# HX711_1.net
KiCad netlist of a schematic drawn in Altium Designer
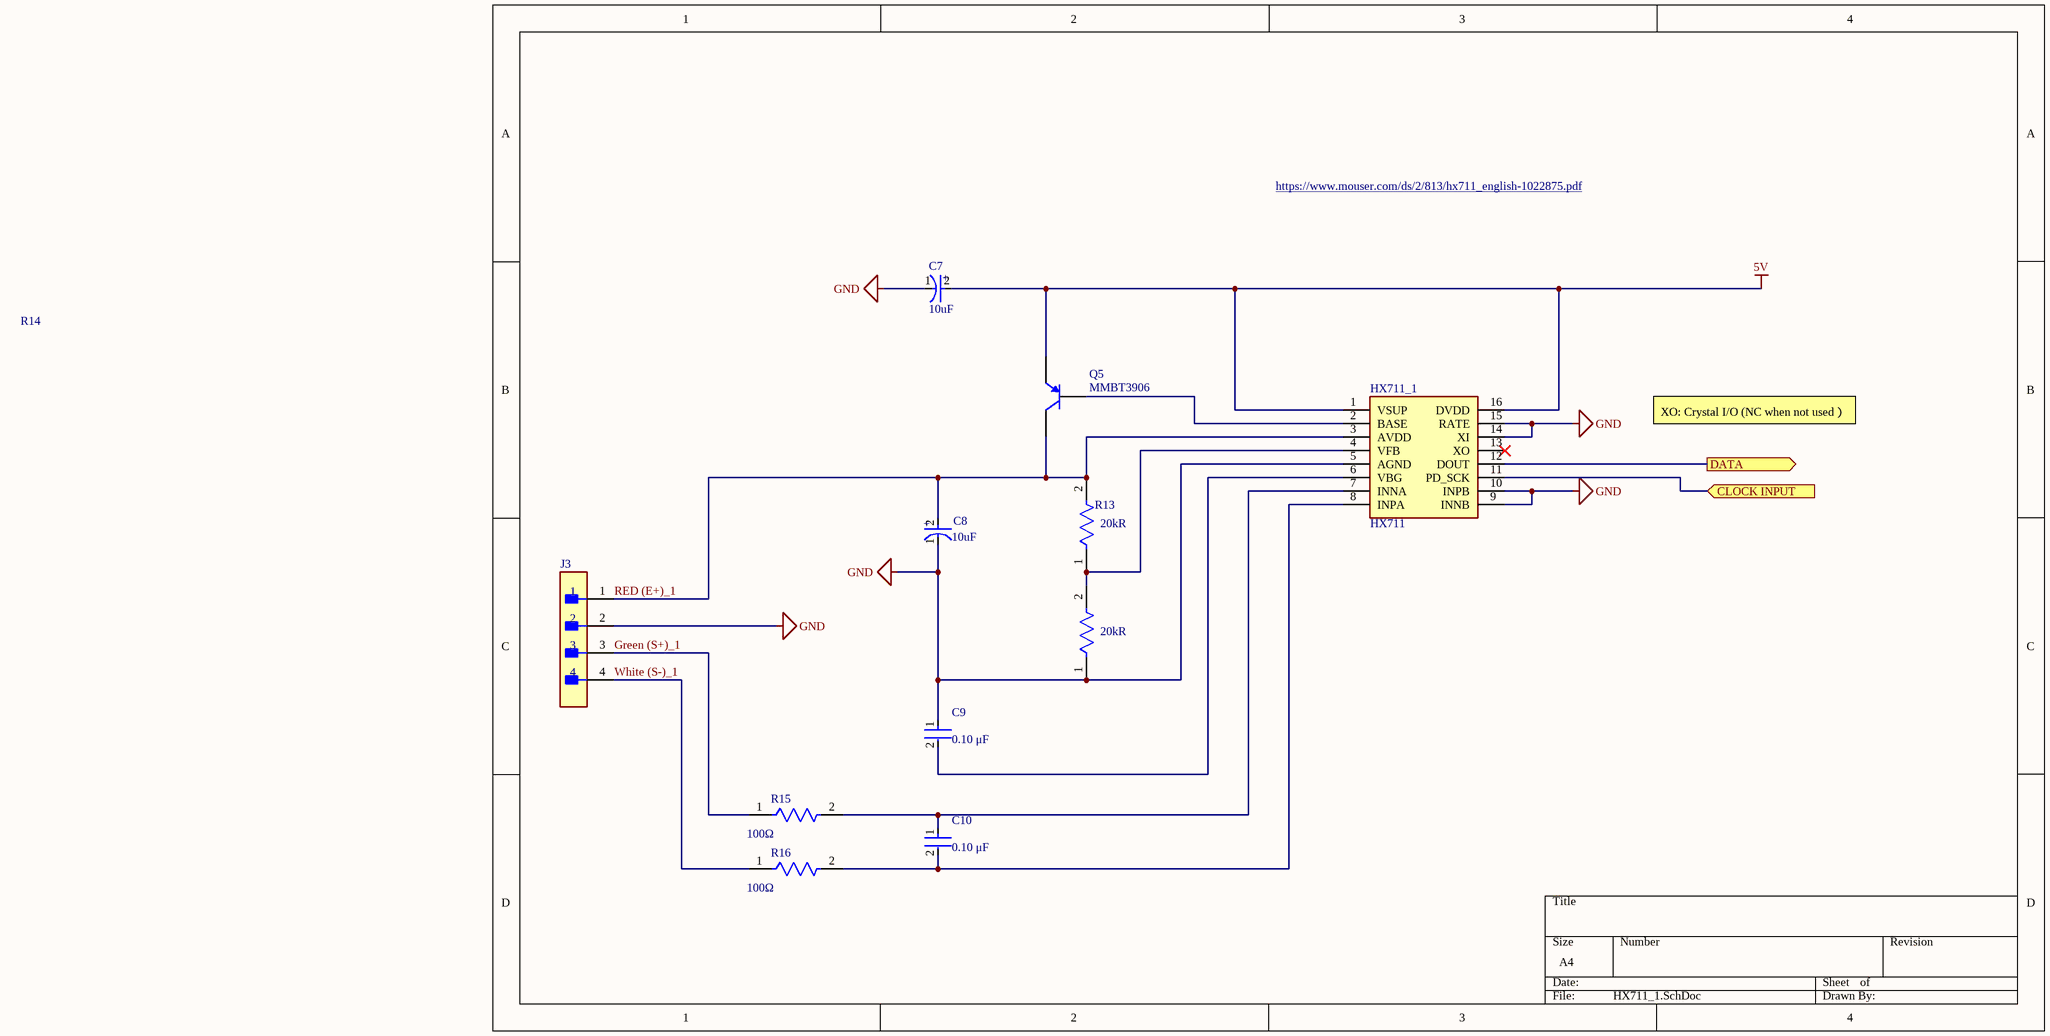
[diagram p0: HX711_1.SchDoc]

(export (version "E")
  (design (tool "Eeschema 10.0.6"))
  (components
    (comp (ref "C7")
      (value "EDK106M035A9BAA")
      (footprint "FP-EDK9B-MFG")
      (description "CAP ALUM 10UF 20% 35V SMD")
      (fields
        (field (name "CAPACITANCE") "10uF")
        (field (name "MANUFACTURER") "Kemet")
        (field (name "OCTOPART") "https://octopart.com/edk106m035a9baa-kemet-26722193")
      )
      (libsource (lib "Altium Content Vault") (part "cf48714ba7e38822c1575c7ec0b6d1f"))
    )
    (comp (ref "C8")
      (value "EDK106M035A9BAA")
      (footprint "FP-EDK9B-MFG")
      (description "CAP ALUM 10UF 20% 35V SMD")
      (fields
        (field (name "CAPACITANCE") "10uF")
        (field (name "MANUFACTURER") "Kemet")
        (field (name "OCTOPART") "https://octopart.com/edk106m035a9baa-kemet-26722193")
      )
      (libsource (lib "Altium Content Vault") (part "cf48714ba7e38822c1575c7ec0b6d1f"))
    )
    (comp (ref "C9")
      (value "0.10 μF")
      (footprint "FP-C0603C-CF-MFG")
      (description "CAP CER 0.1UF 25V X7R 0603")
      (fields
        (field (name "OCTOPART") "https://octopart.com/c0603c104k3rac7411-kemet-9138804")
        (field (name "MANUFACTURER") "KEMET")
      )
      (libsource (lib "Altium Content Vault") (part "b4654b650e69147ec39a6b967a45e02"))
    )
    (comp (ref "C10")
      (value "0.10 μF")
      (footprint "FP-C0603C-CF-MFG")
      (description "CAP CER 0.1UF 25V X7R 0603")
      (fields
        (field (name "OCTOPART") "https://octopart.com/c0603c104k3rac7411-kemet-9138804")
        (field (name "MANUFACTURER") "KEMET")
      )
      (libsource (lib "Altium Content Vault") (part "b4654b650e69147ec39a6b967a45e02"))
    )
    (comp (ref "HX711_1")
      (value "HX711")
      (footprint "SamacSys:SOIC127P600X160-16N")
      (description "Integrated Circuit")
      (libsource (lib "*") (part "HX711"))
    )
    (comp (ref "J3")
      (value "TSW-104-23-T-S")
      (footprint "FP-TSW-104-23-T-S-MFG")
      (description "CONN HEADER VERT 4POS 2.54MM")
      (libsource (lib "Altium Content Vault") (part "f33e0d423099bbb9e64512431cdbdf7"))
    )
    (comp (ref "Q5")
      (value "MMBT3906")
      (footprint "FAIR-SOT23-3_V")
      (description "PNP General-Purpose Amplifier, 40 V, 0.2 A, -55 to 150 degC, 3-Pin SOT23, RoHS, Tape and Reel")
      (fields (field (name "TOLERANCE") "20%"))
      (libsource (lib "Altium Content Vault") (part "BJT-PNP-BEC-3"))
    )
    (comp (ref "R13")
      (value "CRCW060320K0FKEAHP")
      (footprint "FP-CRCW0603-HPe3-MFG")
      (description "RES Thick Film, 20kΩ, 1%, 0.33W, 100ppm/°C, 0603")
      (fields (field (name "RESISTANCE") "20kR") (field (name "TOLERANCE") "1%"))
      (libsource (lib "Altium Content Vault") (part "1029c3af85768c4190bb7ad29bc67b5"))
    )
    (comp (ref "R14")
      (value "CRCW060320K0FKEAHP")
      (footprint "FP-CRCW0603-HPe3-MFG")
      (description "RES Thick Film, 20kΩ, 1%, 0.33W, 100ppm/°C, 0603")
      (fields (field (name "RESISTANCE") "20kR") (field (name "TOLERANCE") "1%"))
      (libsource (lib "Altium Content Vault") (part "1029c3af85768c4190bb7ad29bc67b5"))
    )
    (comp (ref "R15")
      (value "100Ω")
      (footprint "FP-RT0603-MFG")
      (description "RES SMD 100 OHM 1% 1/10W 0603")
      (fields
        (field (name "MANUFACTURER PART NUMBER") "RT0603FRE07100RL")
        (field (name "MANUFACTURER") "Yageo")
      )
      (libsource (lib "Altium Content Vault") (part "1029c3af85768c4190bb7ad29bc67b5"))
    )
    (comp (ref "R16")
      (value "100Ω")
      (footprint "FP-RT0603-MFG")
      (description "RES SMD 100 OHM 1% 1/10W 0603")
      (fields
        (field (name "MANUFACTURER PART NUMBER") "RT0603FRE07100RL")
        (field (name "MANUFACTURER") "Yageo")
      )
      (libsource (lib "Altium Content Vault") (part "1029c3af85768c4190bb7ad29bc67b5"))
    )
  )
  (nets
    (net (code "1") (name "/CLOCK INPUT") (class "Default")
      (node (ref "HX711_1") (pin "11") (pinfunction "PD_SCK_11") (pintype "passive"))
    )
    (net (code "2") (name "/DATA") (class "Default")
      (node (ref "HX711_1") (pin "12") (pinfunction "DOUT_12") (pintype "passive"))
    )
    (net (code "3") (name "/Green (S+)_1") (class "Default")
      (node (ref "J3") (pin "3") (pinfunction "3_3") (pintype "passive"))
      (node (ref "R15") (pin "1") (pinfunction "1_1") (pintype "passive"))
    )
    (net (code "4") (name "/RED (E+)_1") (class "Default")
      (node (ref "C8") (pin "2") (pinfunction "A_2") (pintype "passive"))
      (node (ref "HX711_1") (pin "3") (pinfunction "AVDD_3") (pintype "passive"))
      (node (ref "J3") (pin "1") (pinfunction "1_1") (pintype "passive"))
      (node (ref "Q5") (pin "3") (pinfunction "C_3") (pintype "passive"))
      (node (ref "R13") (pin "2") (pinfunction "2_2") (pintype "passive"))
    )
    (net (code "5") (name "/White (S-)_1") (class "Default")
      (node (ref "J3") (pin "4") (pinfunction "4_4") (pintype "passive"))
      (node (ref "R16") (pin "1") (pinfunction "1_1") (pintype "passive"))
    )
    (net (code "6") (name "5V") (class "Default")
      (node (ref "C7") (pin "2") (pinfunction "A_2") (pintype "passive"))
      (node (ref "HX711_1") (pin "1") (pinfunction "VSUP_1") (pintype "passive"))
      (node (ref "HX711_1") (pin "16") (pinfunction "DVDD_16") (pintype "passive"))
      (node (ref "Q5") (pin "2") (pinfunction "E_2") (pintype "passive"))
    )
    (net (code "7") (name "GND") (class "Default")
      (node (ref "C7") (pin "1") (pinfunction "C_1") (pintype "passive"))
      (node (ref "C8") (pin "1") (pinfunction "C_1") (pintype "passive"))
      (node (ref "C9") (pin "1") (pinfunction "1_1") (pintype "passive"))
      (node (ref "HX711_1") (pin "10") (pinfunction "INPB_10") (pintype "passive"))
      (node (ref "HX711_1") (pin "14") (pinfunction "XI_14") (pintype "passive"))
      (node (ref "HX711_1") (pin "15") (pinfunction "RATE_15") (pintype "passive"))
      (node (ref "HX711_1") (pin "5") (pinfunction "AGND_5") (pintype "passive"))
      (node (ref "HX711_1") (pin "9") (pinfunction "INNB_9") (pintype "passive"))
      (node (ref "J3") (pin "2") (pinfunction "2_2") (pintype "passive"))
      (node (ref "R14") (pin "1") (pinfunction "1_1") (pintype "passive"))
    )
    (net (code "8") (name "Net-(HX711_1-BASE)") (class "Default")
      (node (ref "HX711_1") (pin "2") (pinfunction "BASE_2") (pintype "passive"))
      (node (ref "Q5") (pin "1") (pinfunction "B_1") (pintype "passive"))
    )
    (net (code "9") (name "Net-(HX711_1-INNA)") (class "Default")
      (node (ref "C10") (pin "1") (pinfunction "1_1") (pintype "passive"))
      (node (ref "HX711_1") (pin "7") (pinfunction "INNA_7") (pintype "passive"))
      (node (ref "R15") (pin "2") (pinfunction "2_2") (pintype "passive"))
    )
    (net (code "10") (name "Net-(HX711_1-INPA)") (class "Default")
      (node (ref "C10") (pin "2") (pinfunction "2_2") (pintype "passive"))
      (node (ref "HX711_1") (pin "8") (pinfunction "INPA_8") (pintype "passive"))
      (node (ref "R16") (pin "2") (pinfunction "2_2") (pintype "passive"))
    )
    (net (code "11") (name "Net-(HX711_1-VBG)") (class "Default")
      (node (ref "C9") (pin "2") (pinfunction "2_2") (pintype "passive"))
      (node (ref "HX711_1") (pin "6") (pinfunction "VBG_6") (pintype "passive"))
    )
    (net (code "12") (name "Net-(HX711_1-VFB)") (class "Default")
      (node (ref "HX711_1") (pin "4") (pinfunction "VFB_4") (pintype "passive"))
      (node (ref "R13") (pin "1") (pinfunction "1_1") (pintype "passive"))
      (node (ref "R14") (pin "2") (pinfunction "2_2") (pintype "passive"))
    )
    (net (code "13") (name "unconnected-(HX711_1-XO-Pad13)") (class "Default")
      (node (ref "HX711_1") (pin "13") (pinfunction "XO_13") (pintype "passive+no_connect"))
    )
  )
)
